# OpIoT_jetson_v_1_5.net
KiCad netlist of a schematic drawn in EAGLE
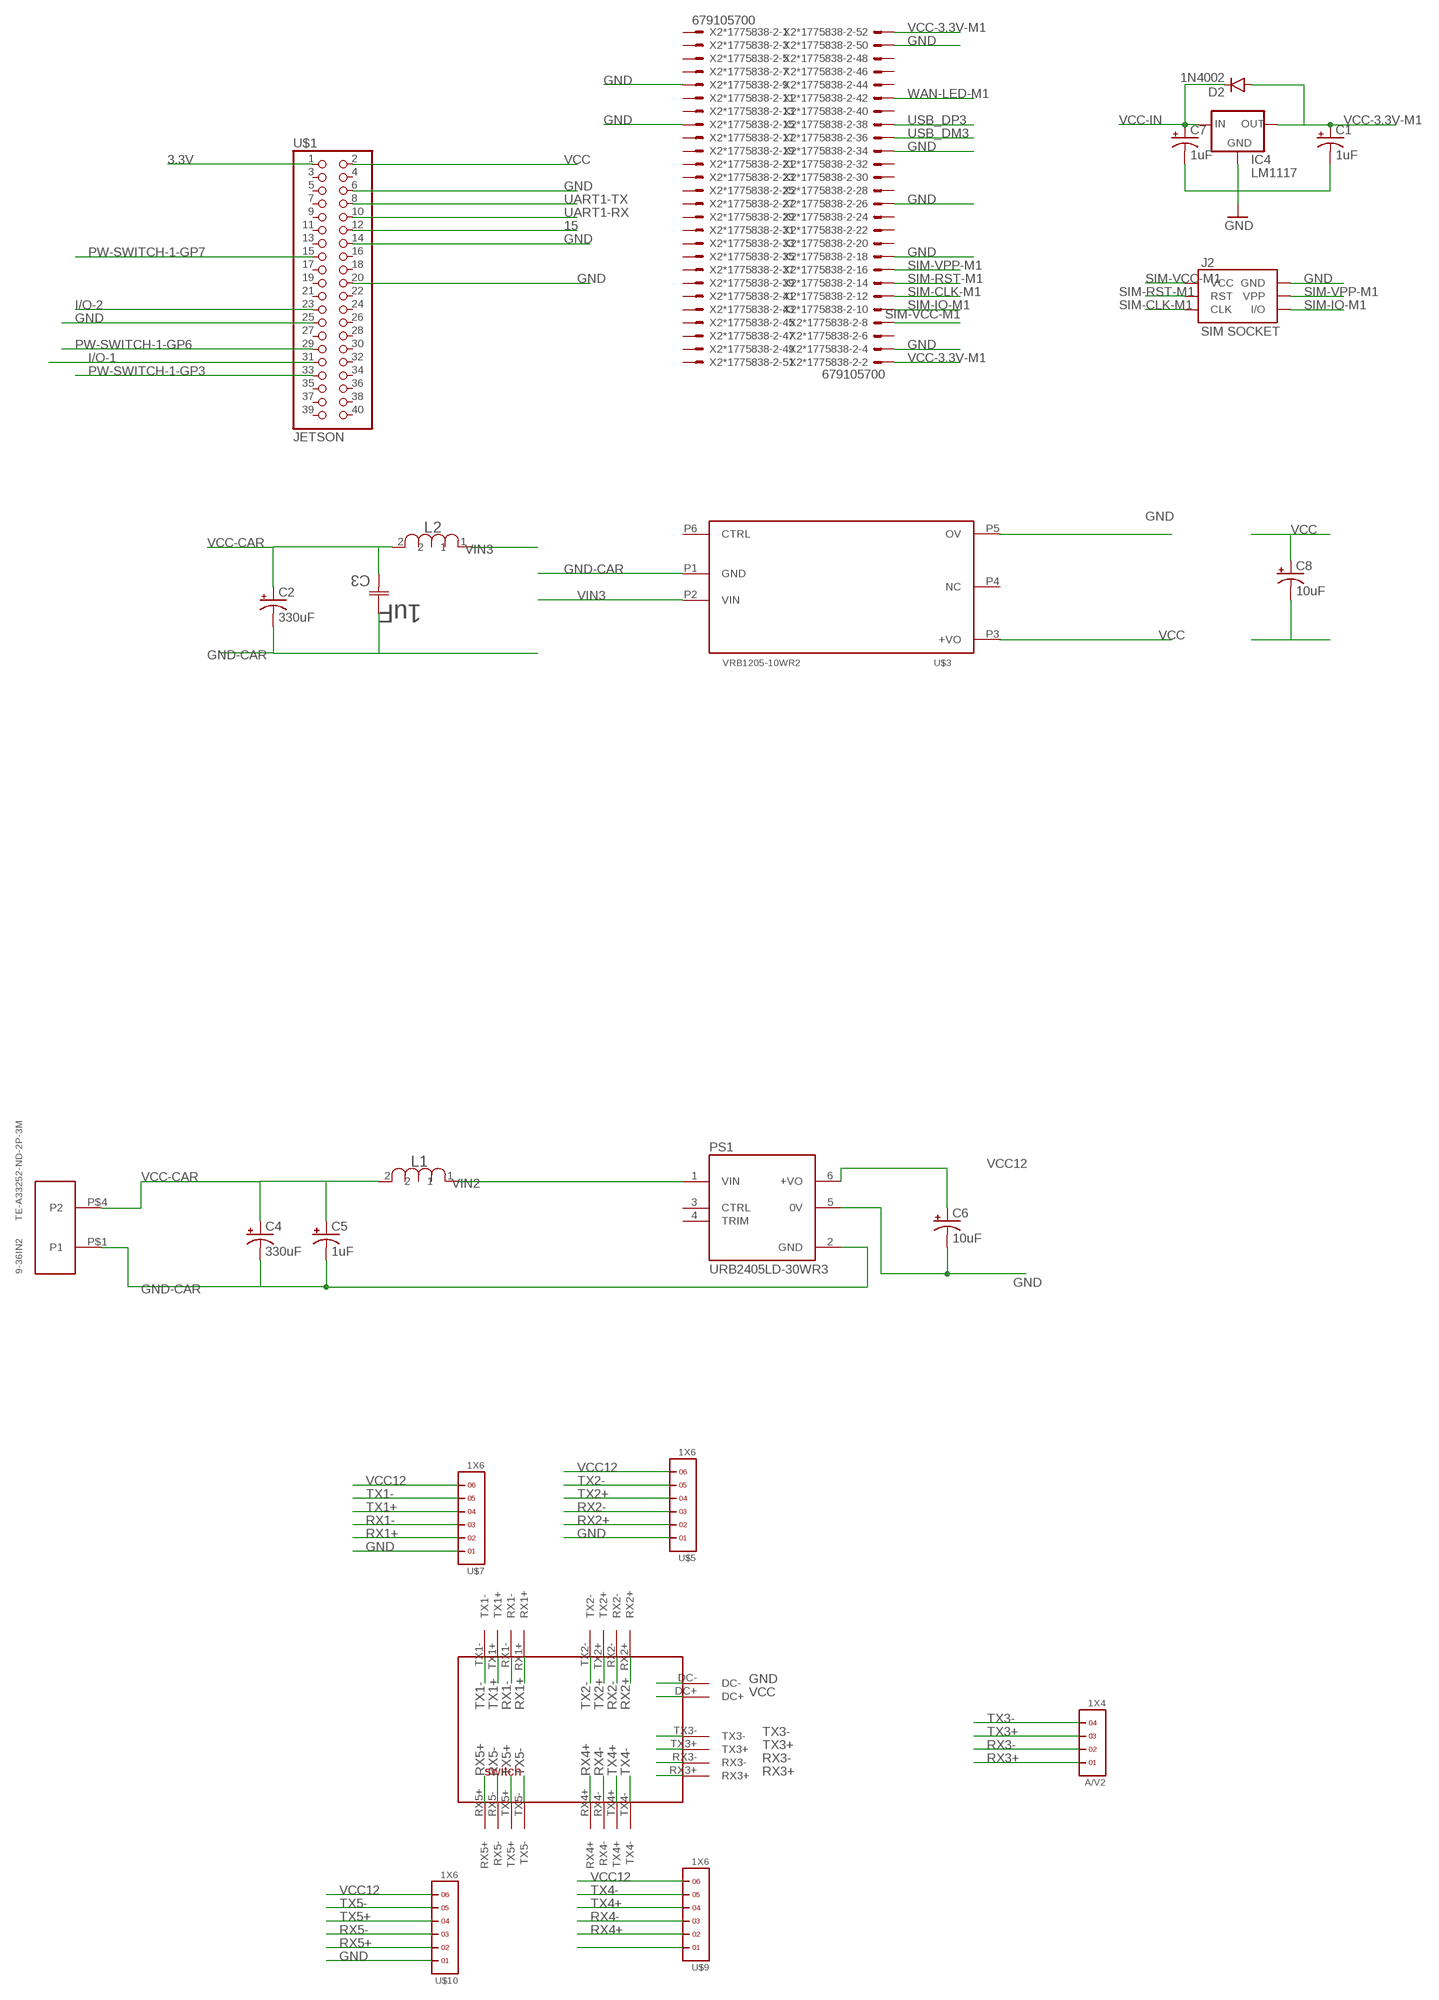
[diagram p0: schematic, sheet 1, part 1 of 3]
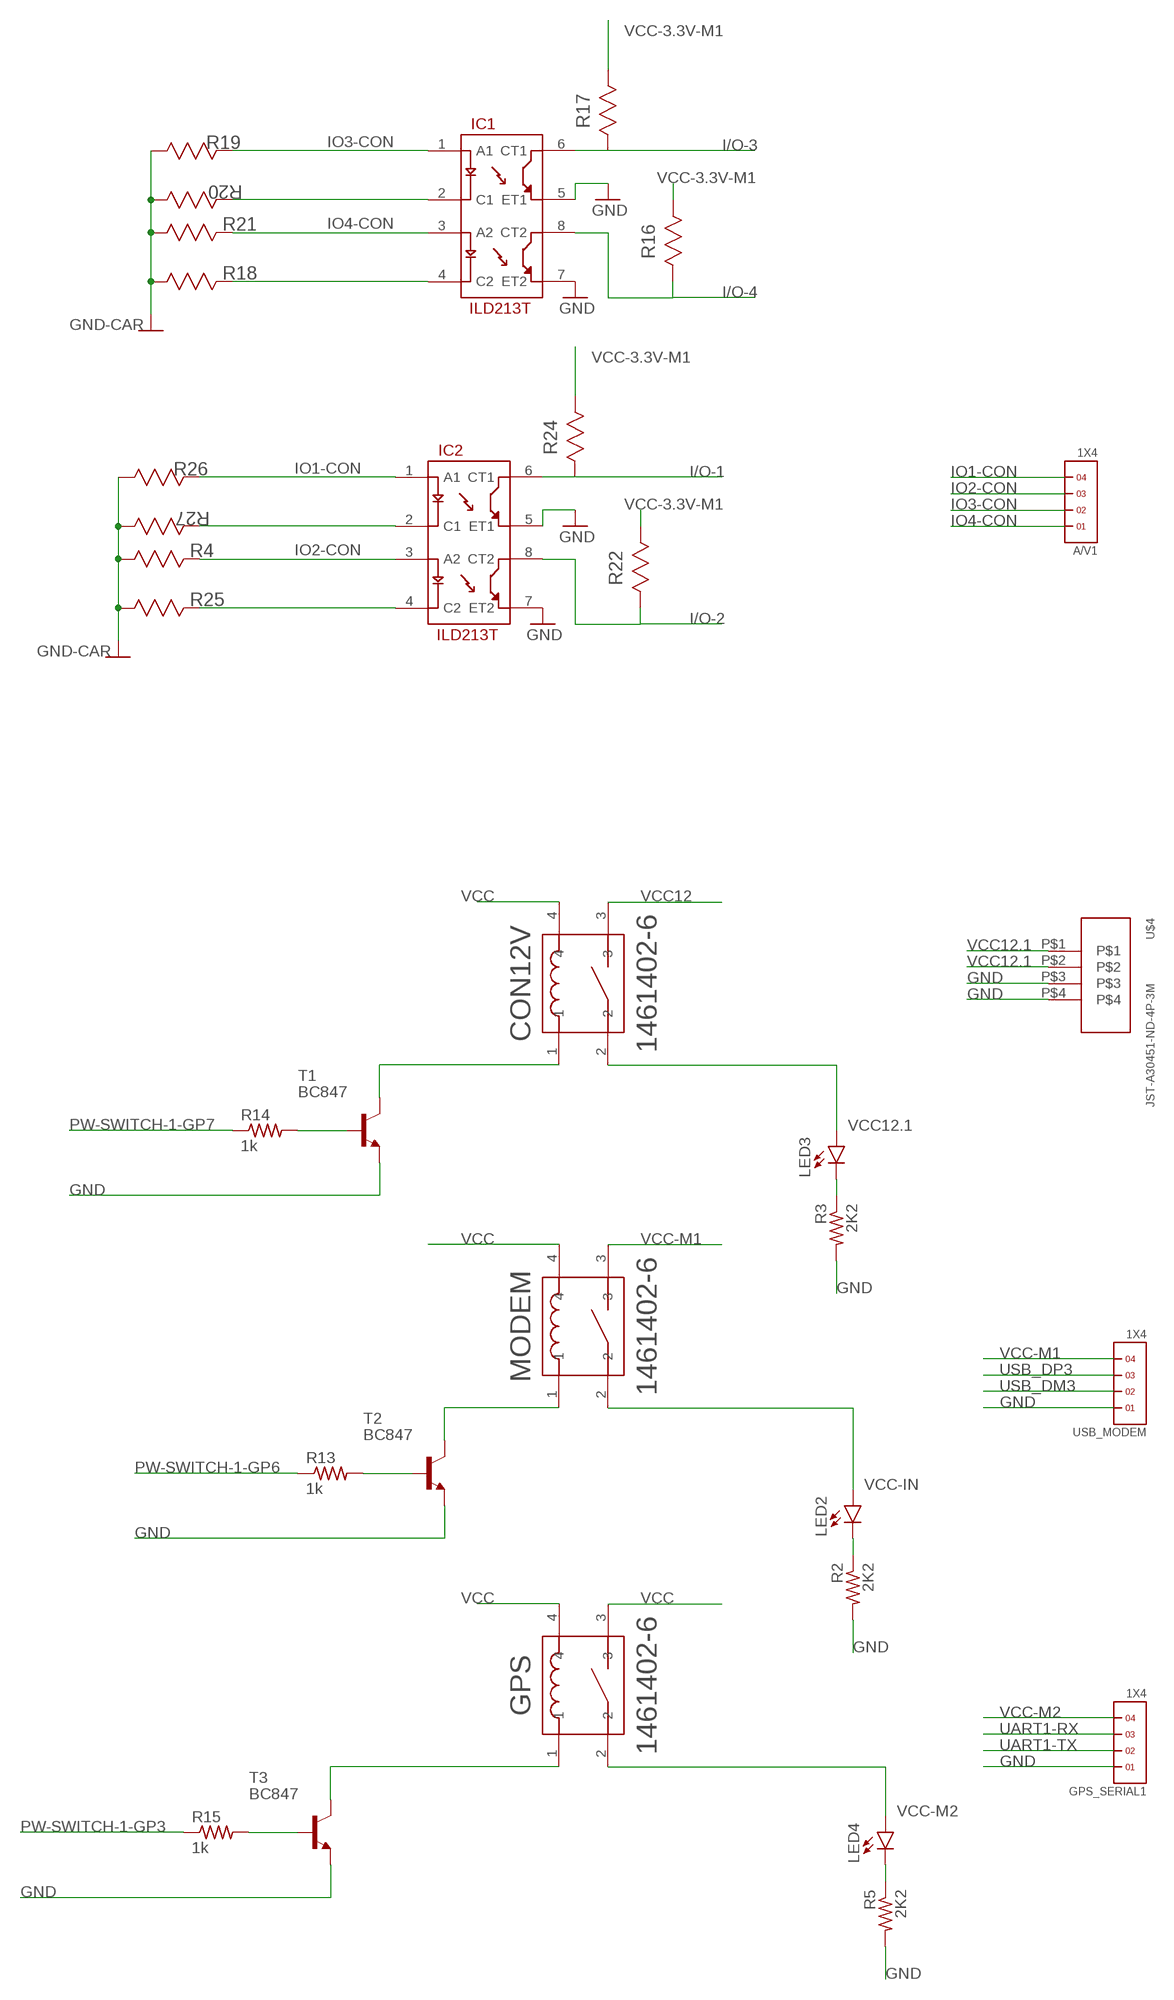
[diagram p1: schematic, sheet 1, part 2 of 3]
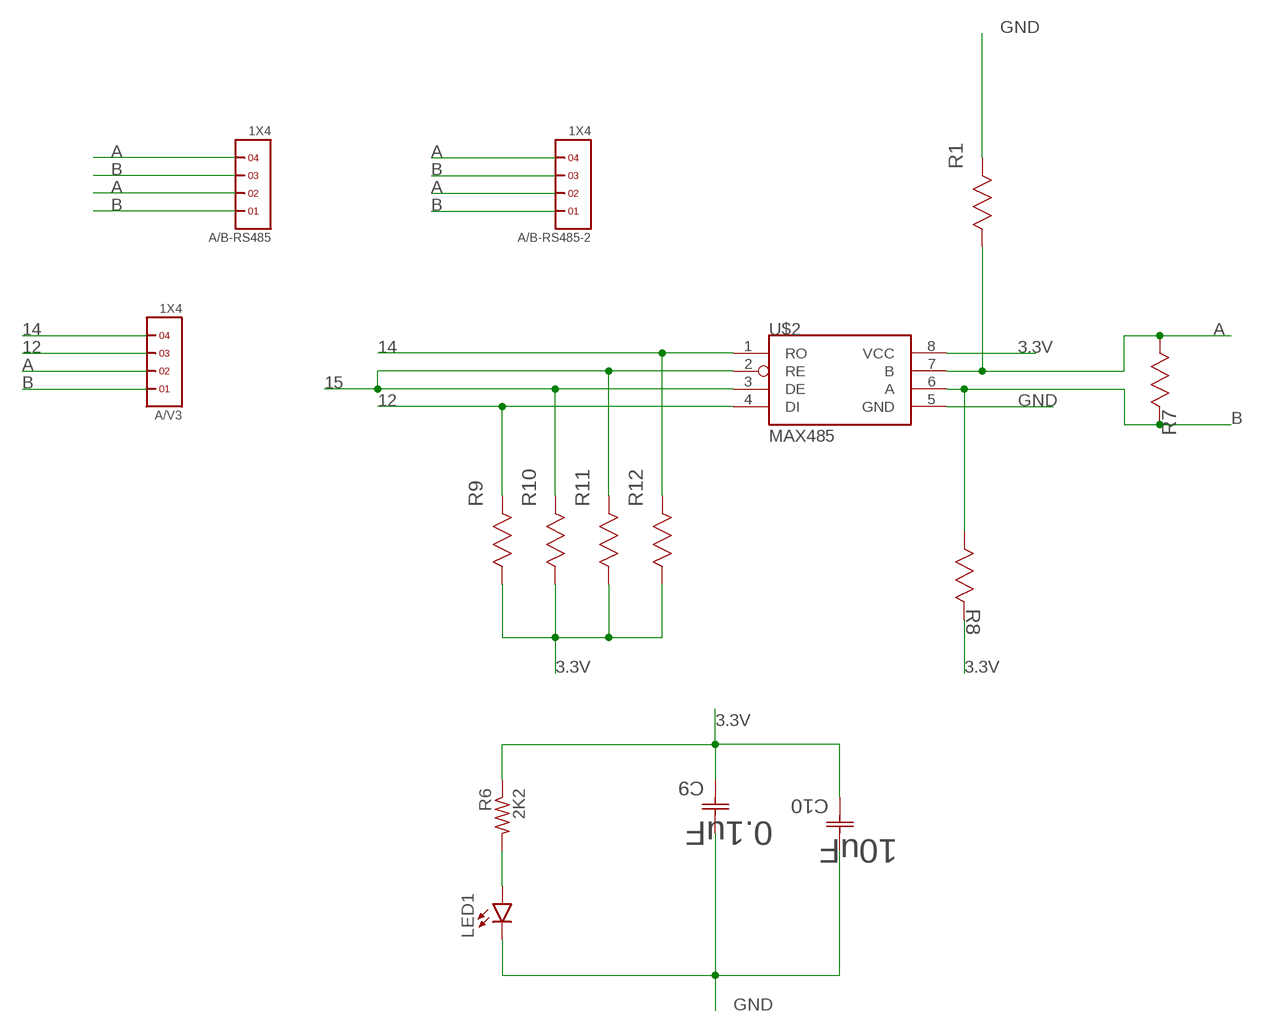
[diagram p2: schematic, sheet 1, part 3 of 3]

(export (version "E")
  (design (tool "Eeschema 10.0.6"))
  (components
    (comp (ref "9-36IN2")
      (value "TE-A33252-ND-2P-3M")
      (footprint "eagle-import:TE-A33252-ND-2P-3M")
      (libsource (lib "eagle-import") (part "TE-A33252-ND-2P-3M"))
    )
    (comp (ref "A/B-RS485")
      (value "1X4")
      (footprint "eagle-import:1X4")
      (libsource (lib "eagle-import") (part "1X4"))
    )
    (comp (ref "A/B-RS485-2")
      (value "1X4")
      (footprint "eagle-import:1X4")
      (libsource (lib "eagle-import") (part "1X4"))
    )
    (comp (ref "A/V1")
      (value "1X4")
      (footprint "eagle-import:1X4")
      (libsource (lib "eagle-import") (part "1X4"))
    )
    (comp (ref "A/V2")
      (value "1X4")
      (footprint "eagle-import:1X4")
      (libsource (lib "eagle-import") (part "1X4"))
    )
    (comp (ref "A/V3")
      (value "1X4")
      (footprint "eagle-import:1X4")
      (libsource (lib "eagle-import") (part "1X4"))
    )
    (comp (ref "C1")
      (value "1uF")
      (footprint "eagle-import:EIA3216-KIT")
      (libsource (lib "eagle-import") (part "CAP_POL1206-KIT"))
    )
    (comp (ref "C2")
      (value "330uF")
      (footprint "eagle-import:UD-10X10_NICHICON")
      (libsource (lib "eagle-import") (part "CPOL-USUD-10X10"))
    )
    (comp (ref "C3")
      (value "1uF")
      (footprint "eagle-import:CAPC3216X110N")
      (fields (field (name "MPN") "C1206C105K5RACTU") (field (name "TOLERANCE") "±10%"))
      (libsource (lib "eagle-import") (part "C1206C105K5RACTU"))
    )
    (comp (ref "C4")
      (value "330uF")
      (footprint "eagle-import:UD-10X10_NICHICON")
      (libsource (lib "eagle-import") (part "CPOL-USUD-10X10"))
    )
    (comp (ref "C5")
      (value "1uF")
      (footprint "eagle-import:EIA3216-KIT")
      (libsource (lib "eagle-import") (part "CAP_POL1206-KIT"))
    )
    (comp (ref "C6")
      (value "10uF")
      (footprint "eagle-import:EIA3216-KIT")
      (libsource (lib "eagle-import") (part "CAP_POL1206-KIT"))
    )
    (comp (ref "C7")
      (value "1uF")
      (footprint "eagle-import:EIA3216-KIT")
      (libsource (lib "eagle-import") (part "CAP_POL1206-KIT"))
    )
    (comp (ref "C8")
      (value "10uF")
      (footprint "eagle-import:EIA3216-KIT")
      (libsource (lib "eagle-import") (part "CAP_POL1206-KIT"))
    )
    (comp (ref "C9")
      (value "0.1uF")
      (footprint "eagle-import:CAPC3216X110N")
      (fields (field (name "MPN") "C1206C105K5RACTU") (field (name "TOLERANCE") "±10%"))
      (libsource (lib "eagle-import") (part "C1206C105K5RACTU"))
    )
    (comp (ref "C10")
      (value "10uF")
      (footprint "eagle-import:CAPC3216X110N")
      (fields (field (name "MPN") "C1206C105K5RACTU") (field (name "TOLERANCE") "±10%"))
      (libsource (lib "eagle-import") (part "C1206C105K5RACTU"))
    )
    (comp (ref "CON12V")
      (value "1461402-6")
      (footprint "eagle-import:RELAY_1461402-6")
      (fields (field (name "MF") "TE Connectivity") (field (name "MP") "OJE-SH-112HM,000"))
      (libsource (lib "eagle-import") (part "1461402-6"))
    )
    (comp (ref "D2")
      (value "1N4002")
      (footprint "eagle-import:SMA-DIODE-KIT")
      (libsource (lib "eagle-import") (part "DIODESMA-KIT"))
    )
    (comp (ref "GPS")
      (value "1461402-6")
      (footprint "eagle-import:RELAY_1461402-6")
      (fields (field (name "MF") "TE Connectivity") (field (name "MP") "OJE-SH-112HM,000"))
      (libsource (lib "eagle-import") (part "1461402-6"))
    )
    (comp (ref "GPS_SERIAL1")
      (value "1X4")
      (footprint "eagle-import:1X4")
      (libsource (lib "eagle-import") (part "1X4"))
    )
    (comp (ref "IC1")
      (value "ILD213T")
      (footprint "eagle-import:SO08")
      (libsource (lib "eagle-import") (part "ILD213T"))
    )
    (comp (ref "IC2")
      (value "ILD213T")
      (footprint "eagle-import:SO08")
      (libsource (lib "eagle-import") (part "ILD213T"))
    )
    (comp (ref "IC4")
      (value "LM1117")
      (footprint "eagle-import:SOT223")
      (fields (field (name "MF") "Texas Instruments") (field (name "MP") "LM1117MP-3.3/NOPB"))
      (libsource (lib "eagle-import") (part "LM1117"))
    )
    (comp (ref "J2")
      (value "SIM SOCKET")
      (footprint "eagle-import:SIMHOLDER")
      (libsource (lib "eagle-import") (part "SIMHOLDERSIM"))
    )
    (comp (ref "L1")
      (value "4.7uH")
      (footprint "eagle-import:INDC3225X22N")
      (fields (field (name "MPN") "PM1210-1R0J-RC") (field (name "TOLERANCE") "±5 %"))
      (libsource (lib "eagle-import") (part "PM1210-1R0J-RC"))
    )
    (comp (ref "L2")
      (value "4.7uH")
      (footprint "eagle-import:INDC3225X22N")
      (fields (field (name "MPN") "PM1210-1R0J-RC") (field (name "TOLERANCE") "±5 %"))
      (libsource (lib "eagle-import") (part "PM1210-1R0J-RC"))
    )
    (comp (ref "LED1")
      (value "LEDCHIPLED_1206")
      (footprint "eagle-import:CHIPLED_1206")
      (libsource (lib "eagle-import") (part "LEDCHIPLED_1206"))
    )
    (comp (ref "LED2")
      (value "LEDCHIPLED_1206")
      (footprint "eagle-import:CHIPLED_1206")
      (libsource (lib "eagle-import") (part "LEDCHIPLED_1206"))
    )
    (comp (ref "LED3")
      (value "LEDCHIPLED_1206")
      (footprint "eagle-import:CHIPLED_1206")
      (libsource (lib "eagle-import") (part "LEDCHIPLED_1206"))
    )
    (comp (ref "LED4")
      (value "LEDCHIPLED_1206")
      (footprint "eagle-import:CHIPLED_1206")
      (libsource (lib "eagle-import") (part "LEDCHIPLED_1206"))
    )
    (comp (ref "MODEM")
      (value "1461402-6")
      (footprint "eagle-import:RELAY_1461402-6")
      (fields (field (name "MF") "TE Connectivity") (field (name "MP") "OJE-SH-112HM,000"))
      (libsource (lib "eagle-import") (part "1461402-6"))
    )
    (comp (ref "PS1")
      (value "URB2405LD-30WR3")
      (footprint "eagle-import:CONV_URB2405LD-30WR3")
      (fields (field (name "MF") "MORNSUN"))
      (libsource (lib "eagle-import") (part "URB2405LD-30WR3"))
    )
    (comp (ref "R1")
      (value "20K")
      (footprint "eagle-import:RESC3216X71N")
      (fields (field (name "MPN") "ERJ-8ENF1501V") (field (name "TOLERANCE") "±1 %"))
      (libsource (lib "eagle-import") (part "ERJ-8ENF1501V"))
    )
    (comp (ref "R2")
      (value "2K2")
      (footprint "eagle-import:M1206")
      (libsource (lib "eagle-import") (part "R-US_M1206"))
    )
    (comp (ref "R3")
      (value "2K2")
      (footprint "eagle-import:M1206")
      (libsource (lib "eagle-import") (part "R-US_M1206"))
    )
    (comp (ref "R4")
      (value "4K7")
      (footprint "eagle-import:RESC3216X71N")
      (fields (field (name "MPN") "ERJ-8ENF1501V") (field (name "TOLERANCE") "±1 %"))
      (libsource (lib "eagle-import") (part "ERJ-8ENF1501V"))
    )
    (comp (ref "R5")
      (value "2K2")
      (footprint "eagle-import:M1206")
      (libsource (lib "eagle-import") (part "R-US_M1206"))
    )
    (comp (ref "R6")
      (value "2K2")
      (footprint "eagle-import:M1206")
      (libsource (lib "eagle-import") (part "R-US_M1206"))
    )
    (comp (ref "R7")
      (value "120")
      (footprint "eagle-import:RESC3216X71N")
      (fields (field (name "MPN") "ERJ-8ENF1501V") (field (name "TOLERANCE") "±1 %"))
      (libsource (lib "eagle-import") (part "ERJ-8ENF1501V"))
    )
    (comp (ref "R8")
      (value "20k")
      (footprint "eagle-import:RESC3216X71N")
      (fields (field (name "MPN") "ERJ-8ENF1501V") (field (name "TOLERANCE") "±1 %"))
      (libsource (lib "eagle-import") (part "ERJ-8ENF1501V"))
    )
    (comp (ref "R9")
      (value "10k")
      (footprint "eagle-import:RESC3216X71N")
      (fields (field (name "MPN") "ERJ-8ENF1501V") (field (name "TOLERANCE") "±1 %"))
      (libsource (lib "eagle-import") (part "ERJ-8ENF1501V"))
    )
    (comp (ref "R10")
      (value "10k")
      (footprint "eagle-import:RESC3216X71N")
      (fields (field (name "MPN") "ERJ-8ENF1501V") (field (name "TOLERANCE") "±1 %"))
      (libsource (lib "eagle-import") (part "ERJ-8ENF1501V"))
    )
    (comp (ref "R11")
      (value "10k")
      (footprint "eagle-import:RESC3216X71N")
      (fields (field (name "MPN") "ERJ-8ENF1501V") (field (name "TOLERANCE") "±1 %"))
      (libsource (lib "eagle-import") (part "ERJ-8ENF1501V"))
    )
    (comp (ref "R12")
      (value "10k")
      (footprint "eagle-import:RESC3216X71N")
      (fields (field (name "MPN") "ERJ-8ENF1501V") (field (name "TOLERANCE") "±1 %"))
      (libsource (lib "eagle-import") (part "ERJ-8ENF1501V"))
    )
    (comp (ref "R13")
      (value "1k")
      (footprint "eagle-import:M1406")
      (libsource (lib "eagle-import") (part "R-US_M1406"))
    )
    (comp (ref "R14")
      (value "1k")
      (footprint "eagle-import:M1406")
      (libsource (lib "eagle-import") (part "R-US_M1406"))
    )
    (comp (ref "R15")
      (value "1k")
      (footprint "eagle-import:M1406")
      (libsource (lib "eagle-import") (part "R-US_M1406"))
    )
    (comp (ref "R16")
      (value "300K")
      (footprint "eagle-import:RESC3216X71N")
      (fields (field (name "MPN") "ERJ-8ENF1501V") (field (name "TOLERANCE") "±1 %"))
      (libsource (lib "eagle-import") (part "ERJ-8ENF1501V"))
    )
    (comp (ref "R17")
      (value "300K")
      (footprint "eagle-import:RESC3216X71N")
      (fields (field (name "MPN") "ERJ-8ENF1501V") (field (name "TOLERANCE") "±1 %"))
      (libsource (lib "eagle-import") (part "ERJ-8ENF1501V"))
    )
    (comp (ref "R18")
      (value "2.2K")
      (footprint "eagle-import:RESC3216X71N")
      (fields (field (name "MPN") "ERJ-8ENF1501V") (field (name "TOLERANCE") "±1 %"))
      (libsource (lib "eagle-import") (part "ERJ-8ENF1501V"))
    )
    (comp (ref "R19")
      (value "4K7")
      (footprint "eagle-import:RESC3216X71N")
      (fields (field (name "MPN") "ERJ-8ENF1501V") (field (name "TOLERANCE") "±1 %"))
      (libsource (lib "eagle-import") (part "ERJ-8ENF1501V"))
    )
    (comp (ref "R20")
      (value "2.2K")
      (footprint "eagle-import:RESC3216X71N")
      (fields (field (name "MPN") "ERJ-8ENF1501V") (field (name "TOLERANCE") "±1 %"))
      (libsource (lib "eagle-import") (part "ERJ-8ENF1501V"))
    )
    (comp (ref "R21")
      (value "4K7")
      (footprint "eagle-import:RESC3216X71N")
      (fields (field (name "MPN") "ERJ-8ENF1501V") (field (name "TOLERANCE") "±1 %"))
      (libsource (lib "eagle-import") (part "ERJ-8ENF1501V"))
    )
    (comp (ref "R22")
      (value "300K")
      (footprint "eagle-import:RESC3216X71N")
      (fields (field (name "MPN") "ERJ-8ENF1501V") (field (name "TOLERANCE") "±1 %"))
      (libsource (lib "eagle-import") (part "ERJ-8ENF1501V"))
    )
    (comp (ref "R24")
      (value "300K")
      (footprint "eagle-import:RESC3216X71N")
      (fields (field (name "MPN") "ERJ-8ENF1501V") (field (name "TOLERANCE") "±1 %"))
      (libsource (lib "eagle-import") (part "ERJ-8ENF1501V"))
    )
    (comp (ref "R25")
      (value "2.2K")
      (footprint "eagle-import:RESC3216X71N")
      (fields (field (name "MPN") "ERJ-8ENF1501V") (field (name "TOLERANCE") "±1 %"))
      (libsource (lib "eagle-import") (part "ERJ-8ENF1501V"))
    )
    (comp (ref "R26")
      (value "ERJ-8ENF1501V")
      (footprint "eagle-import:RESC3216X71N")
      (fields (field (name "TOLERANCE") "±1 %"))
      (libsource (lib "eagle-import") (part "ERJ-8ENF1501V"))
    )
    (comp (ref "R27")
      (value "2.2K")
      (footprint "eagle-import:RESC3216X71N")
      (fields (field (name "MPN") "ERJ-8ENF1501V") (field (name "TOLERANCE") "±1 %"))
      (libsource (lib "eagle-import") (part "ERJ-8ENF1501V"))
    )
    (comp (ref "T1")
      (value "BC847")
      (footprint "eagle-import:SOT23")
      (libsource (lib "eagle-import") (part "BC847"))
    )
    (comp (ref "T2")
      (value "BC847")
      (footprint "eagle-import:SOT23")
      (libsource (lib "eagle-import") (part "BC847"))
    )
    (comp (ref "T3")
      (value "BC847")
      (footprint "eagle-import:SOT23")
      (libsource (lib "eagle-import") (part "BC847"))
    )
    (comp (ref "U$1")
      (value "JETSON")
      (footprint "eagle-import:2X20")
      (libsource (lib "eagle-import") (part "JETSON"))
    )
    (comp (ref "U$2")
      (value "MAX485")
      (footprint "eagle-import:SO08")
      (fields (field (name "MF") "Maxim Integrated"))
      (libsource (lib "eagle-import") (part "MAX485"))
    )
    (comp (ref "U$3")
      (value "VRB1205-10WR2")
      (footprint "eagle-import:MORNSUN-5V")
      (libsource (lib "eagle-import") (part "VRB1205-10WR2"))
    )
    (comp (ref "U$4")
      (value "JST-A30451-ND-4P-3M")
      (footprint "eagle-import:TE-A30451-4P-TH-3M")
      (libsource (lib "eagle-import") (part "JST-A30451-ND-4P-3M"))
    )
    (comp (ref "U$5")
      (value "1X6")
      (footprint "eagle-import:1X6")
      (libsource (lib "eagle-import") (part "1X6"))
    )
    (comp (ref "U$6")
      (value "SWITCH")
      (footprint "eagle-import:JP4")
      (libsource (lib "eagle-import") (part "SWITCH"))
    )
    (comp (ref "U$7")
      (value "1X6")
      (footprint "eagle-import:1X6")
      (libsource (lib "eagle-import") (part "1X6"))
    )
    (comp (ref "U$9")
      (value "1X6")
      (footprint "eagle-import:1X6")
      (libsource (lib "eagle-import") (part "1X6"))
    )
    (comp (ref "U$10")
      (value "1X6")
      (footprint "eagle-import:1X6")
      (libsource (lib "eagle-import") (part "1X6"))
    )
    (comp (ref "USB_MODEM")
      (value "1X4")
      (footprint "eagle-import:1X4")
      (libsource (lib "eagle-import") (part "1X4"))
    )
    (comp (ref "X2*1775838-2")
      (value "679105700")
      (footprint "eagle-import:679105700")
      (fields (field (name "MF") "MOLEX") (field (name "MPN") "67910-5700"))
      (libsource (lib "eagle-import") (part "679105700"))
    )
  )
  (nets
    (net (code "1") (name "/3.3V") (class "Default")
      (node (ref "C10") (pin "2") (pinfunction "C2_2") (pintype "passive"))
      (node (ref "C9") (pin "2") (pinfunction "C2_2") (pintype "passive"))
      (node (ref "R10") (pin "2") (pinfunction "R2_2") (pintype "passive"))
      (node (ref "R11") (pin "2") (pinfunction "R2_2") (pintype "passive"))
      (node (ref "R12") (pin "2") (pinfunction "R2_2") (pintype "passive"))
      (node (ref "R6") (pin "1") (pinfunction "1_1") (pintype "passive"))
      (node (ref "R8") (pin "1") (pinfunction "R1_1") (pintype "passive"))
      (node (ref "R9") (pin "2") (pinfunction "R2_2") (pintype "passive"))
      (node (ref "U$1") (pin "1") (pinfunction "1_1") (pintype "passive"))
      (node (ref "U$2") (pin "8") (pinfunction "VCC_8") (pintype "bidirectional"))
    )
    (net (code "2") (name "/12") (class "Default")
      (node (ref "A/V3") (pin "3") (pinfunction "3_3") (pintype "bidirectional"))
      (node (ref "R9") (pin "1") (pinfunction "R1_1") (pintype "passive"))
      (node (ref "U$2") (pin "4") (pinfunction "DI_4") (pintype "bidirectional"))
    )
    (net (code "3") (name "/14") (class "Default")
      (node (ref "A/V3") (pin "4") (pinfunction "4_4") (pintype "bidirectional"))
      (node (ref "R12") (pin "1") (pinfunction "R1_1") (pintype "passive"))
      (node (ref "U$2") (pin "1") (pinfunction "RO_1") (pintype "bidirectional"))
    )
    (net (code "4") (name "/15") (class "Default")
      (node (ref "R10") (pin "1") (pinfunction "R1_1") (pintype "passive"))
      (node (ref "R11") (pin "1") (pinfunction "R1_1") (pintype "passive"))
      (node (ref "U$1") (pin "12") (pinfunction "12_12") (pintype "passive"))
      (node (ref "U$2") (pin "2") (pinfunction "RE_2") (pintype "bidirectional"))
      (node (ref "U$2") (pin "3") (pinfunction "DE_3") (pintype "bidirectional"))
    )
    (net (code "5") (name "/A") (class "Default")
      (node (ref "A/B-RS485") (pin "2") (pinfunction "2_2") (pintype "bidirectional"))
      (node (ref "A/B-RS485") (pin "4") (pinfunction "4_4") (pintype "bidirectional"))
      (node (ref "A/B-RS485-2") (pin "2") (pinfunction "2_2") (pintype "bidirectional"))
      (node (ref "A/B-RS485-2") (pin "4") (pinfunction "4_4") (pintype "bidirectional"))
      (node (ref "A/V3") (pin "2") (pinfunction "2_2") (pintype "bidirectional"))
      (node (ref "R1") (pin "2") (pinfunction "R2_2") (pintype "passive"))
      (node (ref "R7") (pin "1") (pinfunction "R1_1") (pintype "passive"))
      (node (ref "U$2") (pin "7") (pinfunction "B_7") (pintype "bidirectional"))
    )
    (net (code "6") (name "/B") (class "Default")
      (node (ref "A/B-RS485") (pin "1") (pinfunction "1_1") (pintype "bidirectional"))
      (node (ref "A/B-RS485") (pin "3") (pinfunction "3_3") (pintype "bidirectional"))
      (node (ref "A/B-RS485-2") (pin "1") (pinfunction "1_1") (pintype "bidirectional"))
      (node (ref "A/B-RS485-2") (pin "3") (pinfunction "3_3") (pintype "bidirectional"))
      (node (ref "A/V3") (pin "1") (pinfunction "1_1") (pintype "bidirectional"))
      (node (ref "R7") (pin "2") (pinfunction "R2_2") (pintype "passive"))
      (node (ref "R8") (pin "2") (pinfunction "R2_2") (pintype "passive"))
      (node (ref "U$2") (pin "6") (pinfunction "A_6") (pintype "bidirectional"))
    )
    (net (code "7") (name "/IO1-CON") (class "Default")
      (node (ref "A/V1") (pin "4") (pinfunction "4_4") (pintype "bidirectional"))
      (node (ref "IC2") (pin "1") (pinfunction "A1_1") (pintype "bidirectional"))
      (node (ref "R26") (pin "1") (pinfunction "R1_1") (pintype "passive"))
    )
    (net (code "8") (name "/IO2-CON") (class "Default")
      (node (ref "A/V1") (pin "3") (pinfunction "3_3") (pintype "bidirectional"))
      (node (ref "IC2") (pin "3") (pinfunction "A2_3") (pintype "bidirectional"))
      (node (ref "R4") (pin "1") (pinfunction "R1_1") (pintype "passive"))
    )
    (net (code "9") (name "/IO3-CON") (class "Default")
      (node (ref "A/V1") (pin "2") (pinfunction "2_2") (pintype "bidirectional"))
      (node (ref "IC1") (pin "1") (pinfunction "A1_1") (pintype "bidirectional"))
      (node (ref "R19") (pin "1") (pinfunction "R1_1") (pintype "passive"))
    )
    (net (code "10") (name "/IO4-CON") (class "Default")
      (node (ref "A/V1") (pin "1") (pinfunction "1_1") (pintype "bidirectional"))
      (node (ref "IC1") (pin "3") (pinfunction "A2_3") (pintype "bidirectional"))
      (node (ref "R21") (pin "1") (pinfunction "R1_1") (pintype "passive"))
    )
    (net (code "11") (name "/I{slash}O-1") (class "Default")
      (node (ref "IC2") (pin "6") (pinfunction "CT1_6") (pintype "bidirectional"))
      (node (ref "R24") (pin "2") (pinfunction "R2_2") (pintype "passive"))
      (node (ref "U$1") (pin "31") (pinfunction "31_31") (pintype "passive"))
    )
    (net (code "12") (name "/I{slash}O-2") (class "Default")
      (node (ref "IC2") (pin "8") (pinfunction "CT2_8") (pintype "bidirectional"))
      (node (ref "R22") (pin "2") (pinfunction "R2_2") (pintype "passive"))
      (node (ref "U$1") (pin "23") (pinfunction "23_23") (pintype "passive"))
    )
    (net (code "13") (name "/I{slash}O-3") (class "Default")
      (node (ref "IC1") (pin "6") (pinfunction "CT1_6") (pintype "bidirectional"))
      (node (ref "R17") (pin "2") (pinfunction "R2_2") (pintype "passive"))
    )
    (net (code "14") (name "/I{slash}O-4") (class "Default")
      (node (ref "IC1") (pin "8") (pinfunction "CT2_8") (pintype "bidirectional"))
      (node (ref "R16") (pin "2") (pinfunction "R2_2") (pintype "passive"))
    )
    (net (code "15") (name "/PW-SWITCH-1-GP3") (class "Default")
      (node (ref "R15") (pin "1") (pinfunction "1_1") (pintype "passive"))
      (node (ref "U$1") (pin "33") (pinfunction "33_33") (pintype "passive"))
    )
    (net (code "16") (name "/PW-SWITCH-1-GP6") (class "Default")
      (node (ref "R13") (pin "1") (pinfunction "1_1") (pintype "passive"))
      (node (ref "U$1") (pin "29") (pinfunction "29_29") (pintype "passive"))
    )
    (net (code "17") (name "/PW-SWITCH-1-GP7") (class "Default")
      (node (ref "R14") (pin "1") (pinfunction "1_1") (pintype "passive"))
      (node (ref "U$1") (pin "15") (pinfunction "15_15") (pintype "passive"))
    )
    (net (code "18") (name "/RX1+") (class "Default")
      (node (ref "U$6") (pin "RX1+") (pinfunction "RX1+_RX1+") (pintype "bidirectional"))
      (node (ref "U$7") (pin "2") (pinfunction "2_2") (pintype "bidirectional"))
    )
    (net (code "19") (name "/RX1-") (class "Default")
      (node (ref "U$6") (pin "RX1-") (pinfunction "RX1-_RX1-") (pintype "bidirectional"))
      (node (ref "U$7") (pin "3") (pinfunction "3_3") (pintype "bidirectional"))
    )
    (net (code "20") (name "/RX2+") (class "Default")
      (node (ref "U$5") (pin "2") (pinfunction "2_2") (pintype "bidirectional"))
      (node (ref "U$6") (pin "RX2+") (pinfunction "RX2+_RX2+") (pintype "bidirectional"))
    )
    (net (code "21") (name "/RX2-") (class "Default")
      (node (ref "U$5") (pin "3") (pinfunction "3_3") (pintype "bidirectional"))
      (node (ref "U$6") (pin "RX2-") (pinfunction "RX2-_RX2-") (pintype "bidirectional"))
    )
    (net (code "22") (name "/RX3+") (class "Default")
      (node (ref "A/V2") (pin "1") (pinfunction "1_1") (pintype "bidirectional"))
      (node (ref "U$6") (pin "RX3+") (pinfunction "RX3+_RX3+") (pintype "bidirectional"))
    )
    (net (code "23") (name "/RX3-") (class "Default")
      (node (ref "A/V2") (pin "2") (pinfunction "2_2") (pintype "bidirectional"))
      (node (ref "U$6") (pin "RX3-") (pinfunction "RX3-_RX3-") (pintype "bidirectional"))
    )
    (net (code "24") (name "/RX4+") (class "Default")
      (node (ref "U$6") (pin "RX4+") (pinfunction "RX4+_RX4+") (pintype "bidirectional"))
      (node (ref "U$9") (pin "2") (pinfunction "2_2") (pintype "bidirectional"))
    )
    (net (code "25") (name "/RX4-") (class "Default")
      (node (ref "U$6") (pin "RX4-") (pinfunction "RX4-_RX4-") (pintype "bidirectional"))
      (node (ref "U$9") (pin "3") (pinfunction "3_3") (pintype "bidirectional"))
    )
    (net (code "26") (name "/RX5+") (class "Default")
      (node (ref "U$10") (pin "2") (pinfunction "2_2") (pintype "bidirectional"))
      (node (ref "U$6") (pin "RX5+") (pinfunction "RX5+_RX5+") (pintype "bidirectional"))
    )
    (net (code "27") (name "/RX5-") (class "Default")
      (node (ref "U$10") (pin "3") (pinfunction "3_3") (pintype "bidirectional"))
      (node (ref "U$6") (pin "RX5-") (pinfunction "RX5-_RX5-") (pintype "bidirectional"))
    )
    (net (code "28") (name "/SIM-CLK-M1") (class "Default")
      (node (ref "J2") (pin "C3") (pinfunction "CLK_C3") (pintype "input"))
      (node (ref "X2*1775838-2") (pin "12") (pinfunction "S_12") (pintype "passive"))
    )
    (net (code "29") (name "/SIM-IO-M1") (class "Default")
      (node (ref "J2") (pin "C7") (pinfunction "I/O_C7") (pintype "bidirectional"))
      (node (ref "X2*1775838-2") (pin "10") (pinfunction "S_10") (pintype "passive"))
    )
    (net (code "30") (name "/SIM-RST-M1") (class "Default")
      (node (ref "J2") (pin "C2") (pinfunction "RST_C2") (pintype "input"))
      (node (ref "X2*1775838-2") (pin "14") (pinfunction "S_14") (pintype "passive"))
    )
    (net (code "31") (name "/SIM-VCC-M1") (class "Default")
      (node (ref "J2") (pin "C1") (pinfunction "VCC_C1") (pintype "power_in"))
      (node (ref "X2*1775838-2") (pin "8") (pinfunction "S_8") (pintype "passive"))
    )
    (net (code "32") (name "/SIM-VPP-M1") (class "Default")
      (node (ref "J2") (pin "C6") (pinfunction "VPP_C6") (pintype "input"))
      (node (ref "X2*1775838-2") (pin "16") (pinfunction "S_16") (pintype "passive"))
    )
    (net (code "33") (name "/TX1+") (class "Default")
      (node (ref "U$6") (pin "TX1+") (pinfunction "TX1+_TX1+") (pintype "bidirectional"))
      (node (ref "U$7") (pin "4") (pinfunction "4_4") (pintype "bidirectional"))
    )
    (net (code "34") (name "/TX1-") (class "Default")
      (node (ref "U$6") (pin "TX1-") (pinfunction "TX1-_TX1-") (pintype "bidirectional"))
      (node (ref "U$7") (pin "5") (pinfunction "5_5") (pintype "bidirectional"))
    )
    (net (code "35") (name "/TX2+") (class "Default")
      (node (ref "U$5") (pin "4") (pinfunction "4_4") (pintype "bidirectional"))
      (node (ref "U$6") (pin "TX2+") (pinfunction "TX2+_TX2+") (pintype "bidirectional"))
    )
    (net (code "36") (name "/TX2-") (class "Default")
      (node (ref "U$5") (pin "5") (pinfunction "5_5") (pintype "bidirectional"))
      (node (ref "U$6") (pin "TX2-") (pinfunction "TX2-_TX2-") (pintype "bidirectional"))
    )
    (net (code "37") (name "/TX3+") (class "Default")
      (node (ref "A/V2") (pin "3") (pinfunction "3_3") (pintype "bidirectional"))
      (node (ref "U$6") (pin "TX3+") (pinfunction "TX3+_TX3+") (pintype "bidirectional"))
    )
    (net (code "38") (name "/TX3-") (class "Default")
      (node (ref "A/V2") (pin "4") (pinfunction "4_4") (pintype "bidirectional"))
      (node (ref "U$6") (pin "TX3-") (pinfunction "TX3-_TX3-") (pintype "bidirectional"))
    )
    (net (code "39") (name "/TX4+") (class "Default")
      (node (ref "U$6") (pin "TX4+") (pinfunction "TX4+_TX4+") (pintype "bidirectional"))
      (node (ref "U$9") (pin "4") (pinfunction "4_4") (pintype "bidirectional"))
    )
    (net (code "40") (name "/TX4-") (class "Default")
      (node (ref "U$6") (pin "TX4-") (pinfunction "TX4-_TX4-") (pintype "bidirectional"))
      (node (ref "U$9") (pin "5") (pinfunction "5_5") (pintype "bidirectional"))
    )
    (net (code "41") (name "/TX5+") (class "Default")
      (node (ref "U$10") (pin "4") (pinfunction "4_4") (pintype "bidirectional"))
      (node (ref "U$6") (pin "TX5+") (pinfunction "TX5+_TX5+") (pintype "bidirectional"))
    )
    (net (code "42") (name "/TX5-") (class "Default")
      (node (ref "U$10") (pin "5") (pinfunction "5_5") (pintype "bidirectional"))
      (node (ref "U$6") (pin "TX5-") (pinfunction "TX5-_TX5-") (pintype "bidirectional"))
    )
    (net (code "43") (name "/UART1-RX") (class "Default")
      (node (ref "GPS_SERIAL1") (pin "3") (pinfunction "3_3") (pintype "bidirectional"))
      (node (ref "U$1") (pin "10") (pinfunction "10_10") (pintype "passive"))
    )
    (net (code "44") (name "/UART1-TX") (class "Default")
      (node (ref "GPS_SERIAL1") (pin "2") (pinfunction "2_2") (pintype "bidirectional"))
      (node (ref "U$1") (pin "8") (pinfunction "8_8") (pintype "passive"))
    )
    (net (code "45") (name "/USB_DM3") (class "Default")
      (node (ref "USB_MODEM") (pin "2") (pinfunction "2_2") (pintype "bidirectional"))
      (node (ref "X2*1775838-2") (pin "36") (pinfunction "S_36") (pintype "passive"))
    )
    (net (code "46") (name "/USB_DP3") (class "Default")
      (node (ref "USB_MODEM") (pin "3") (pinfunction "3_3") (pintype "bidirectional"))
      (node (ref "X2*1775838-2") (pin "38") (pinfunction "S_38") (pintype "passive"))
    )
    (net (code "47") (name "/VCC") (class "Default")
      (node (ref "C8") (pin "A") (pinfunction "+_A") (pintype "passive"))
      (node (ref "CON12V") (pin "4") (pinfunction "4_4") (pintype "passive"))
      (node (ref "GPS") (pin "3") (pinfunction "3_3") (pintype "passive"))
      (node (ref "GPS") (pin "4") (pinfunction "4_4") (pintype "passive"))
      (node (ref "MODEM") (pin "4") (pinfunction "4_4") (pintype "passive"))
      (node (ref "U$1") (pin "2") (pinfunction "2_2") (pintype "passive"))
      (node (ref "U$3") (pin "P3") (pinfunction "+VO_P3") (pintype "output"))
      (node (ref "U$6") (pin "DC+") (pinfunction "DC+_DC+") (pintype "bidirectional"))
    )
    (net (code "48") (name "/VCC-3.3V-M1") (class "Default")
      (node (ref "C1") (pin "A") (pinfunction "+_A") (pintype "passive"))
      (node (ref "D2") (pin "A") (pinfunction "A_A") (pintype "passive"))
      (node (ref "IC4") (pin "2") (pinfunction "OUT_2") (pintype "passive"))
      (node (ref "R16") (pin "1") (pinfunction "R1_1") (pintype "passive"))
      (node (ref "R17") (pin "1") (pinfunction "R1_1") (pintype "passive"))
      (node (ref "R22") (pin "1") (pinfunction "R1_1") (pintype "passive"))
      (node (ref "R24") (pin "1") (pinfunction "R1_1") (pintype "passive"))
      (node (ref "X2*1775838-2") (pin "2") (pinfunction "S_2") (pintype "passive"))
      (node (ref "X2*1775838-2") (pin "52") (pinfunction "S_52") (pintype "passive"))
    )
    (net (code "49") (name "/VCC-CAR") (class "Default")
      (node (ref "9-36IN2") (pin "P$4") (pinfunction "P2_P$4") (pintype "bidirectional"))
      (node (ref "C2") (pin "+") (pinfunction "+_+") (pintype "passive"))
      (node (ref "C3") (pin "2") (pinfunction "C2_2") (pintype "passive"))
      (node (ref "C4") (pin "+") (pinfunction "+_+") (pintype "passive"))
      (node (ref "C5") (pin "A") (pinfunction "+_A") (pintype "passive"))
      (node (ref "L1") (pin "2") (pinfunction "2_2") (pintype "passive"))
      (node (ref "L2") (pin "2") (pinfunction "2_2") (pintype "passive"))
    )
    (net (code "50") (name "/VCC-IN") (class "Default")
      (node (ref "C7") (pin "A") (pinfunction "+_A") (pintype "passive"))
      (node (ref "D2") (pin "C") (pinfunction "C_C") (pintype "passive"))
      (node (ref "IC4") (pin "3") (pinfunction "IN_3") (pintype "input"))
      (node (ref "LED2") (pin "A") (pinfunction "A_A") (pintype "passive"))
      (node (ref "MODEM") (pin "2") (pinfunction "2_2") (pintype "passive"))
    )
    (net (code "51") (name "/VCC-M1") (class "Default")
      (node (ref "MODEM") (pin "3") (pinfunction "3_3") (pintype "passive"))
      (node (ref "USB_MODEM") (pin "4") (pinfunction "4_4") (pintype "bidirectional"))
    )
    (net (code "52") (name "/VCC-M2") (class "Default")
      (node (ref "GPS") (pin "2") (pinfunction "2_2") (pintype "passive"))
      (node (ref "GPS_SERIAL1") (pin "4") (pinfunction "4_4") (pintype "bidirectional"))
      (node (ref "LED4") (pin "A") (pinfunction "A_A") (pintype "passive"))
    )
    (net (code "53") (name "/VCC12") (class "Default")
      (node (ref "C6") (pin "A") (pinfunction "+_A") (pintype "passive"))
      (node (ref "CON12V") (pin "3") (pinfunction "3_3") (pintype "passive"))
      (node (ref "PS1") (pin "6") (pinfunction "+VO_6") (pintype "output"))
      (node (ref "U$10") (pin "6") (pinfunction "6_6") (pintype "bidirectional"))
      (node (ref "U$5") (pin "6") (pinfunction "6_6") (pintype "bidirectional"))
      (node (ref "U$7") (pin "6") (pinfunction "6_6") (pintype "bidirectional"))
      (node (ref "U$9") (pin "6") (pinfunction "6_6") (pintype "bidirectional"))
    )
    (net (code "54") (name "/VCC12.1") (class "Default")
      (node (ref "CON12V") (pin "2") (pinfunction "2_2") (pintype "passive"))
      (node (ref "LED3") (pin "A") (pinfunction "A_A") (pintype "passive"))
      (node (ref "U$4") (pin "P$1") (pinfunction "P$1_P$1") (pintype "bidirectional"))
      (node (ref "U$4") (pin "P$2") (pinfunction "P$2_P$2") (pintype "bidirectional"))
    )
    (net (code "55") (name "/VIN2") (class "Default")
      (node (ref "L1") (pin "1") (pinfunction "1_1") (pintype "passive"))
      (node (ref "PS1") (pin "1") (pinfunction "VIN_1") (pintype "input"))
    )
    (net (code "56") (name "/VIN3") (class "Default")
      (node (ref "L2") (pin "1") (pinfunction "1_1") (pintype "passive"))
      (node (ref "U$3") (pin "P2") (pinfunction "VIN_P2") (pintype "bidirectional"))
    )
    (net (code "57") (name "/WAN-LED-M1") (class "Default")
      (node (ref "X2*1775838-2") (pin "42") (pinfunction "S_42") (pintype "passive"))
    )
    (net (code "58") (name "GND") (class "Default")
      (node (ref "C1") (pin "C") (pinfunction "-_C") (pintype "passive"))
      (node (ref "C10") (pin "1") (pinfunction "C1_1") (pintype "passive"))
      (node (ref "C6") (pin "C") (pinfunction "-_C") (pintype "passive"))
      (node (ref "C7") (pin "C") (pinfunction "-_C") (pintype "passive"))
      (node (ref "C8") (pin "C") (pinfunction "-_C") (pintype "passive"))
      (node (ref "C9") (pin "1") (pinfunction "C1_1") (pintype "passive"))
      (node (ref "GPS_SERIAL1") (pin "1") (pinfunction "1_1") (pintype "bidirectional"))
      (node (ref "IC1") (pin "5") (pinfunction "ET1_5") (pintype "bidirectional"))
      (node (ref "IC1") (pin "7") (pinfunction "ET2_7") (pintype "bidirectional"))
      (node (ref "IC2") (pin "5") (pinfunction "ET1_5") (pintype "bidirectional"))
      (node (ref "IC2") (pin "7") (pinfunction "ET2_7") (pintype "bidirectional"))
      (node (ref "IC4") (pin "1") (pinfunction "GND_1") (pintype "input"))
      (node (ref "J2") (pin "C5") (pinfunction "GND_C5") (pintype "power_in"))
      (node (ref "LED1") (pin "C") (pinfunction "C_C") (pintype "passive"))
      (node (ref "PS1") (pin "5") (pinfunction "0V_5") (pintype "output"))
      (node (ref "R1") (pin "1") (pinfunction "R1_1") (pintype "passive"))
      (node (ref "R2") (pin "2") (pinfunction "2_2") (pintype "passive"))
      (node (ref "R3") (pin "2") (pinfunction "2_2") (pintype "passive"))
      (node (ref "R5") (pin "2") (pinfunction "2_2") (pintype "passive"))
      (node (ref "T1") (pin "2") (pinfunction "E_2") (pintype "passive"))
      (node (ref "T2") (pin "2") (pinfunction "E_2") (pintype "passive"))
      (node (ref "T3") (pin "2") (pinfunction "E_2") (pintype "passive"))
      (node (ref "U$1") (pin "14") (pinfunction "14_14") (pintype "passive"))
      (node (ref "U$1") (pin "20") (pinfunction "20_20") (pintype "passive"))
      (node (ref "U$1") (pin "25") (pinfunction "25_25") (pintype "passive"))
      (node (ref "U$1") (pin "6") (pinfunction "6_6") (pintype "passive"))
      (node (ref "U$10") (pin "1") (pinfunction "1_1") (pintype "bidirectional"))
      (node (ref "U$2") (pin "5") (pinfunction "GND_5") (pintype "bidirectional"))
      (node (ref "U$3") (pin "P5") (pinfunction "OV_P5") (pintype "output"))
      (node (ref "U$4") (pin "P$3") (pinfunction "P$3_P$3") (pintype "bidirectional"))
      (node (ref "U$4") (pin "P$4") (pinfunction "P$4_P$4") (pintype "bidirectional"))
      (node (ref "U$5") (pin "1") (pinfunction "1_1") (pintype "bidirectional"))
      (node (ref "U$6") (pin "DC-") (pinfunction "DC-_DC-") (pintype "bidirectional"))
      (node (ref "U$7") (pin "1") (pinfunction "1_1") (pintype "bidirectional"))
      (node (ref "U$9") (pin "1") (pinfunction "1_1") (pintype "bidirectional"))
      (node (ref "USB_MODEM") (pin "1") (pinfunction "1_1") (pintype "bidirectional"))
      (node (ref "X2*1775838-2") (pin "15") (pinfunction "S_15") (pintype "passive"))
      (node (ref "X2*1775838-2") (pin "18") (pinfunction "S_18") (pintype "passive"))
      (node (ref "X2*1775838-2") (pin "26") (pinfunction "S_26") (pintype "passive"))
      (node (ref "X2*1775838-2") (pin "34") (pinfunction "S_34") (pintype "passive"))
      (node (ref "X2*1775838-2") (pin "4") (pinfunction "S_4") (pintype "passive"))
      (node (ref "X2*1775838-2") (pin "50") (pinfunction "S_50") (pintype "passive"))
      (node (ref "X2*1775838-2") (pin "9") (pinfunction "S_9") (pintype "passive"))
    )
    (net (code "59") (name "GND-CAR") (class "Default")
      (node (ref "9-36IN2") (pin "P$1") (pinfunction "P1_P$1") (pintype "bidirectional"))
      (node (ref "C2") (pin "-") (pinfunction "-_-") (pintype "passive"))
      (node (ref "C3") (pin "1") (pinfunction "C1_1") (pintype "passive"))
      (node (ref "C4") (pin "-") (pinfunction "-_-") (pintype "passive"))
      (node (ref "C5") (pin "C") (pinfunction "-_C") (pintype "passive"))
      (node (ref "PS1") (pin "2") (pinfunction "GND_2") (pintype "power_in"))
      (node (ref "R18") (pin "1") (pinfunction "R1_1") (pintype "passive"))
      (node (ref "R19") (pin "2") (pinfunction "R2_2") (pintype "passive"))
      (node (ref "R20") (pin "1") (pinfunction "R1_1") (pintype "passive"))
      (node (ref "R21") (pin "2") (pinfunction "R2_2") (pintype "passive"))
      (node (ref "R25") (pin "1") (pinfunction "R1_1") (pintype "passive"))
      (node (ref "R26") (pin "2") (pinfunction "R2_2") (pintype "passive"))
      (node (ref "R27") (pin "1") (pinfunction "R1_1") (pintype "passive"))
      (node (ref "R4") (pin "2") (pinfunction "R2_2") (pintype "passive"))
      (node (ref "U$3") (pin "P1") (pinfunction "GND_P1") (pintype "bidirectional"))
    )
    (net (code "60") (name "Net-(IC1-C1)") (class "Default")
      (node (ref "IC1") (pin "2") (pinfunction "C1_2") (pintype "bidirectional"))
      (node (ref "R20") (pin "2") (pinfunction "R2_2") (pintype "passive"))
    )
    (net (code "61") (name "Net-(IC1-C2)") (class "Default")
      (node (ref "IC1") (pin "4") (pinfunction "C2_4") (pintype "bidirectional"))
      (node (ref "R18") (pin "2") (pinfunction "R2_2") (pintype "passive"))
    )
    (net (code "62") (name "Net-(IC2-C1)") (class "Default")
      (node (ref "IC2") (pin "2") (pinfunction "C1_2") (pintype "bidirectional"))
      (node (ref "R27") (pin "2") (pinfunction "R2_2") (pintype "passive"))
    )
    (net (code "63") (name "Net-(IC2-C2)") (class "Default")
      (node (ref "IC2") (pin "4") (pinfunction "C2_4") (pintype "bidirectional"))
      (node (ref "R25") (pin "2") (pinfunction "R2_2") (pintype "passive"))
    )
    (net (code "64") (name "Net-(LED1-PadA)") (class "Default")
      (node (ref "LED1") (pin "A") (pinfunction "A_A") (pintype "passive"))
      (node (ref "R6") (pin "2") (pinfunction "2_2") (pintype "passive"))
    )
    (net (code "65") (name "Net-(LED2-PadC)") (class "Default")
      (node (ref "LED2") (pin "C") (pinfunction "C_C") (pintype "passive"))
      (node (ref "R2") (pin "1") (pinfunction "1_1") (pintype "passive"))
    )
    (net (code "66") (name "Net-(LED3-PadC)") (class "Default")
      (node (ref "LED3") (pin "C") (pinfunction "C_C") (pintype "passive"))
      (node (ref "R3") (pin "1") (pinfunction "1_1") (pintype "passive"))
    )
    (net (code "67") (name "Net-(LED4-PadC)") (class "Default")
      (node (ref "LED4") (pin "C") (pinfunction "C_C") (pintype "passive"))
      (node (ref "R5") (pin "1") (pinfunction "1_1") (pintype "passive"))
    )
    (net (code "68") (name "Net-(T1-B)") (class "Default")
      (node (ref "R14") (pin "2") (pinfunction "2_2") (pintype "passive"))
      (node (ref "T1") (pin "1") (pinfunction "B_1") (pintype "passive"))
    )
    (net (code "69") (name "Net-(T1-C)") (class "Default")
      (node (ref "CON12V") (pin "1") (pinfunction "1_1") (pintype "passive"))
      (node (ref "T1") (pin "3") (pinfunction "C_3") (pintype "passive"))
    )
    (net (code "70") (name "Net-(T2-B)") (class "Default")
      (node (ref "R13") (pin "2") (pinfunction "2_2") (pintype "passive"))
      (node (ref "T2") (pin "1") (pinfunction "B_1") (pintype "passive"))
    )
    (net (code "71") (name "Net-(T2-C)") (class "Default")
      (node (ref "MODEM") (pin "1") (pinfunction "1_1") (pintype "passive"))
      (node (ref "T2") (pin "3") (pinfunction "C_3") (pintype "passive"))
    )
    (net (code "72") (name "Net-(T3-B)") (class "Default")
      (node (ref "R15") (pin "2") (pinfunction "2_2") (pintype "passive"))
      (node (ref "T3") (pin "1") (pinfunction "B_1") (pintype "passive"))
    )
    (net (code "73") (name "Net-(T3-C)") (class "Default")
      (node (ref "GPS") (pin "1") (pinfunction "1_1") (pintype "passive"))
      (node (ref "T3") (pin "3") (pinfunction "C_3") (pintype "passive"))
    )
    (net (code "74") (name "unconnected-(PS1-CTRL-Pad3)") (class "Default")
      (node (ref "PS1") (pin "3") (pinfunction "CTRL_3") (pintype "input"))
    )
    (net (code "75") (name "unconnected-(PS1-TRIM-Pad4)") (class "Default")
      (node (ref "PS1") (pin "4") (pinfunction "TRIM_4") (pintype "input"))
    )
    (net (code "76") (name "unconnected-(U$1-Pad3)") (class "Default")
      (node (ref "U$1") (pin "3") (pinfunction "3_3") (pintype "passive"))
    )
    (net (code "77") (name "unconnected-(U$1-Pad4)") (class "Default")
      (node (ref "U$1") (pin "4") (pinfunction "4_4") (pintype "passive"))
    )
    (net (code "78") (name "unconnected-(U$1-Pad5)") (class "Default")
      (node (ref "U$1") (pin "5") (pinfunction "5_5") (pintype "passive"))
    )
    (net (code "79") (name "unconnected-(U$1-Pad7)") (class "Default")
      (node (ref "U$1") (pin "7") (pinfunction "7_7") (pintype "passive"))
    )
    (net (code "80") (name "unconnected-(U$1-Pad9)") (class "Default")
      (node (ref "U$1") (pin "9") (pinfunction "9_9") (pintype "passive"))
    )
    (net (code "81") (name "unconnected-(U$1-Pad11)") (class "Default")
      (node (ref "U$1") (pin "11") (pinfunction "11_11") (pintype "passive"))
    )
    (net (code "82") (name "unconnected-(U$1-Pad13)") (class "Default")
      (node (ref "U$1") (pin "13") (pinfunction "13_13") (pintype "passive"))
    )
    (net (code "83") (name "unconnected-(U$1-Pad16)") (class "Default")
      (node (ref "U$1") (pin "16") (pinfunction "16_16") (pintype "passive"))
    )
    (net (code "84") (name "unconnected-(U$1-Pad17)") (class "Default")
      (node (ref "U$1") (pin "17") (pinfunction "17_17") (pintype "passive"))
    )
    (net (code "85") (name "unconnected-(U$1-Pad18)") (class "Default")
      (node (ref "U$1") (pin "18") (pinfunction "18_18") (pintype "passive"))
    )
    (net (code "86") (name "unconnected-(U$1-Pad19)") (class "Default")
      (node (ref "U$1") (pin "19") (pinfunction "19_19") (pintype "passive"))
    )
    (net (code "87") (name "unconnected-(U$1-Pad21)") (class "Default")
      (node (ref "U$1") (pin "21") (pinfunction "21_21") (pintype "passive"))
    )
    (net (code "88") (name "unconnected-(U$1-Pad22)") (class "Default")
      (node (ref "U$1") (pin "22") (pinfunction "22_22") (pintype "passive"))
    )
    (net (code "89") (name "unconnected-(U$1-Pad24)") (class "Default")
      (node (ref "U$1") (pin "24") (pinfunction "24_24") (pintype "passive"))
    )
    (net (code "90") (name "unconnected-(U$1-Pad26)") (class "Default")
      (node (ref "U$1") (pin "26") (pinfunction "26_26") (pintype "passive"))
    )
    (net (code "91") (name "unconnected-(U$1-Pad27)") (class "Default")
      (node (ref "U$1") (pin "27") (pinfunction "27_27") (pintype "passive"))
    )
    (net (code "92") (name "unconnected-(U$1-Pad28)") (class "Default")
      (node (ref "U$1") (pin "28") (pinfunction "28_28") (pintype "passive"))
    )
    (net (code "93") (name "unconnected-(U$1-Pad30)") (class "Default")
      (node (ref "U$1") (pin "30") (pinfunction "30_30") (pintype "passive"))
    )
    (net (code "94") (name "unconnected-(U$1-Pad32)") (class "Default")
      (node (ref "U$1") (pin "32") (pinfunction "32_32") (pintype "passive"))
    )
    (net (code "95") (name "unconnected-(U$1-Pad34)") (class "Default")
      (node (ref "U$1") (pin "34") (pinfunction "34_34") (pintype "passive"))
    )
    (net (code "96") (name "unconnected-(U$1-Pad35)") (class "Default")
      (node (ref "U$1") (pin "35") (pinfunction "35_35") (pintype "passive"))
    )
    (net (code "97") (name "unconnected-(U$1-Pad36)") (class "Default")
      (node (ref "U$1") (pin "36") (pinfunction "36_36") (pintype "passive"))
    )
    (net (code "98") (name "unconnected-(U$1-Pad37)") (class "Default")
      (node (ref "U$1") (pin "37") (pinfunction "37_37") (pintype "passive"))
    )
    (net (code "99") (name "unconnected-(U$1-Pad38)") (class "Default")
      (node (ref "U$1") (pin "38") (pinfunction "38_38") (pintype "passive"))
    )
    (net (code "100") (name "unconnected-(U$1-Pad39)") (class "Default")
      (node (ref "U$1") (pin "39") (pinfunction "39_39") (pintype "passive"))
    )
    (net (code "101") (name "unconnected-(U$1-Pad40)") (class "Default")
      (node (ref "U$1") (pin "40") (pinfunction "40_40") (pintype "passive"))
    )
    (net (code "102") (name "unconnected-(U$3-CTRL-PadP6)") (class "Default")
      (node (ref "U$3") (pin "P6") (pinfunction "CTRL_P6") (pintype "bidirectional"))
    )
    (net (code "103") (name "unconnected-(U$3-NC-PadP4)") (class "Default")
      (node (ref "U$3") (pin "P4") (pinfunction "NC_P4") (pintype "output"))
    )
    (net (code "104") (name "unconnected-(X2*1775838-2A-S-Pad1)") (class "Default")
      (node (ref "X2*1775838-2") (pin "1") (pinfunction "S_1") (pintype "passive"))
    )
    (net (code "105") (name "unconnected-(X2*1775838-2AA-S-Pad33)") (class "Default")
      (node (ref "X2*1775838-2") (pin "33") (pinfunction "S_33") (pintype "passive"))
    )
    (net (code "106") (name "unconnected-(X2*1775838-2AC-S-Pad35)") (class "Default")
      (node (ref "X2*1775838-2") (pin "35") (pinfunction "S_35") (pintype "passive"))
    )
    (net (code "107") (name "unconnected-(X2*1775838-2AE-S-Pad37)") (class "Default")
      (node (ref "X2*1775838-2") (pin "37") (pinfunction "S_37") (pintype "passive"))
    )
    (net (code "108") (name "unconnected-(X2*1775838-2AG-S-Pad39)") (class "Default")
      (node (ref "X2*1775838-2") (pin "39") (pinfunction "S_39") (pintype "passive"))
    )
    (net (code "109") (name "unconnected-(X2*1775838-2AI-S-Pad40)") (class "Default")
      (node (ref "X2*1775838-2") (pin "40") (pinfunction "S_40") (pintype "passive"))
    )
    (net (code "110") (name "unconnected-(X2*1775838-2AJ-S-Pad41)") (class "Default")
      (node (ref "X2*1775838-2") (pin "41") (pinfunction "S_41") (pintype "passive"))
    )
    (net (code "111") (name "unconnected-(X2*1775838-2AL-S-Pad43)") (class "Default")
      (node (ref "X2*1775838-2") (pin "43") (pinfunction "S_43") (pintype "passive"))
    )
    (net (code "112") (name "unconnected-(X2*1775838-2AM-S-Pad44)") (class "Default")
      (node (ref "X2*1775838-2") (pin "44") (pinfunction "S_44") (pintype "passive"))
    )
    (net (code "113") (name "unconnected-(X2*1775838-2AN-S-Pad45)") (class "Default")
      (node (ref "X2*1775838-2") (pin "45") (pinfunction "S_45") (pintype "passive"))
    )
    (net (code "114") (name "unconnected-(X2*1775838-2AO-S-Pad46)") (class "Default")
      (node (ref "X2*1775838-2") (pin "46") (pinfunction "S_46") (pintype "passive"))
    )
    (net (code "115") (name "unconnected-(X2*1775838-2AP-S-Pad47)") (class "Default")
      (node (ref "X2*1775838-2") (pin "47") (pinfunction "S_47") (pintype "passive"))
    )
    (net (code "116") (name "unconnected-(X2*1775838-2AQ-S-Pad48)") (class "Default")
      (node (ref "X2*1775838-2") (pin "48") (pinfunction "S_48") (pintype "passive"))
    )
    (net (code "117") (name "unconnected-(X2*1775838-2AR-S-Pad49)") (class "Default")
      (node (ref "X2*1775838-2") (pin "49") (pinfunction "S_49") (pintype "passive"))
    )
    (net (code "118") (name "unconnected-(X2*1775838-2AS-S-Pad5)") (class "Default")
      (node (ref "X2*1775838-2") (pin "5") (pinfunction "S_5") (pintype "passive"))
    )
    (net (code "119") (name "unconnected-(X2*1775838-2AU-S-Pad51)") (class "Default")
      (node (ref "X2*1775838-2") (pin "51") (pinfunction "S_51") (pintype "passive"))
    )
    (net (code "120") (name "unconnected-(X2*1775838-2AW-S-Pad6)") (class "Default")
      (node (ref "X2*1775838-2") (pin "6") (pinfunction "S_6") (pintype "passive"))
    )
    (net (code "121") (name "unconnected-(X2*1775838-2AX-S-Pad7)") (class "Default")
      (node (ref "X2*1775838-2") (pin "7") (pinfunction "S_7") (pintype "passive"))
    )
    (net (code "122") (name "unconnected-(X2*1775838-2C-S-Pad11)") (class "Default")
      (node (ref "X2*1775838-2") (pin "11") (pinfunction "S_11") (pintype "passive"))
    )
    (net (code "123") (name "unconnected-(X2*1775838-2E-S-Pad13)") (class "Default")
      (node (ref "X2*1775838-2") (pin "13") (pinfunction "S_13") (pintype "passive"))
    )
    (net (code "124") (name "unconnected-(X2*1775838-2I-S-Pad17)") (class "Default")
      (node (ref "X2*1775838-2") (pin "17") (pinfunction "S_17") (pintype "passive"))
    )
    (net (code "125") (name "unconnected-(X2*1775838-2K-S-Pad19)") (class "Default")
      (node (ref "X2*1775838-2") (pin "19") (pinfunction "S_19") (pintype "passive"))
    )
    (net (code "126") (name "unconnected-(X2*1775838-2M-S-Pad20)") (class "Default")
      (node (ref "X2*1775838-2") (pin "20") (pinfunction "S_20") (pintype "passive"))
    )
    (net (code "127") (name "unconnected-(X2*1775838-2N-S-Pad21)") (class "Default")
      (node (ref "X2*1775838-2") (pin "21") (pinfunction "S_21") (pintype "passive"))
    )
    (net (code "128") (name "unconnected-(X2*1775838-2O-S-Pad22)") (class "Default")
      (node (ref "X2*1775838-2") (pin "22") (pinfunction "S_22") (pintype "passive"))
    )
    (net (code "129") (name "unconnected-(X2*1775838-2P-S-Pad23)") (class "Default")
      (node (ref "X2*1775838-2") (pin "23") (pinfunction "S_23") (pintype "passive"))
    )
    (net (code "130") (name "unconnected-(X2*1775838-2Q-S-Pad24)") (class "Default")
      (node (ref "X2*1775838-2") (pin "24") (pinfunction "S_24") (pintype "passive"))
    )
    (net (code "131") (name "unconnected-(X2*1775838-2R-S-Pad25)") (class "Default")
      (node (ref "X2*1775838-2") (pin "25") (pinfunction "S_25") (pintype "passive"))
    )
    (net (code "132") (name "unconnected-(X2*1775838-2T-S-Pad27)") (class "Default")
      (node (ref "X2*1775838-2") (pin "27") (pinfunction "S_27") (pintype "passive"))
    )
    (net (code "133") (name "unconnected-(X2*1775838-2U-S-Pad28)") (class "Default")
      (node (ref "X2*1775838-2") (pin "28") (pinfunction "S_28") (pintype "passive"))
    )
    (net (code "134") (name "unconnected-(X2*1775838-2V-S-Pad29)") (class "Default")
      (node (ref "X2*1775838-2") (pin "29") (pinfunction "S_29") (pintype "passive"))
    )
    (net (code "135") (name "unconnected-(X2*1775838-2W-S-Pad3)") (class "Default")
      (node (ref "X2*1775838-2") (pin "3") (pinfunction "S_3") (pintype "passive"))
    )
    (net (code "136") (name "unconnected-(X2*1775838-2X-S-Pad30)") (class "Default")
      (node (ref "X2*1775838-2") (pin "30") (pinfunction "S_30") (pintype "passive"))
    )
    (net (code "137") (name "unconnected-(X2*1775838-2Y-S-Pad31)") (class "Default")
      (node (ref "X2*1775838-2") (pin "31") (pinfunction "S_31") (pintype "passive"))
    )
    (net (code "138") (name "unconnected-(X2*1775838-2Z-S-Pad32)") (class "Default")
      (node (ref "X2*1775838-2") (pin "32") (pinfunction "S_32") (pintype "passive"))
    )
  )
)
